# BLDC.net
KiCad netlist of a schematic drawn in Altium Designer
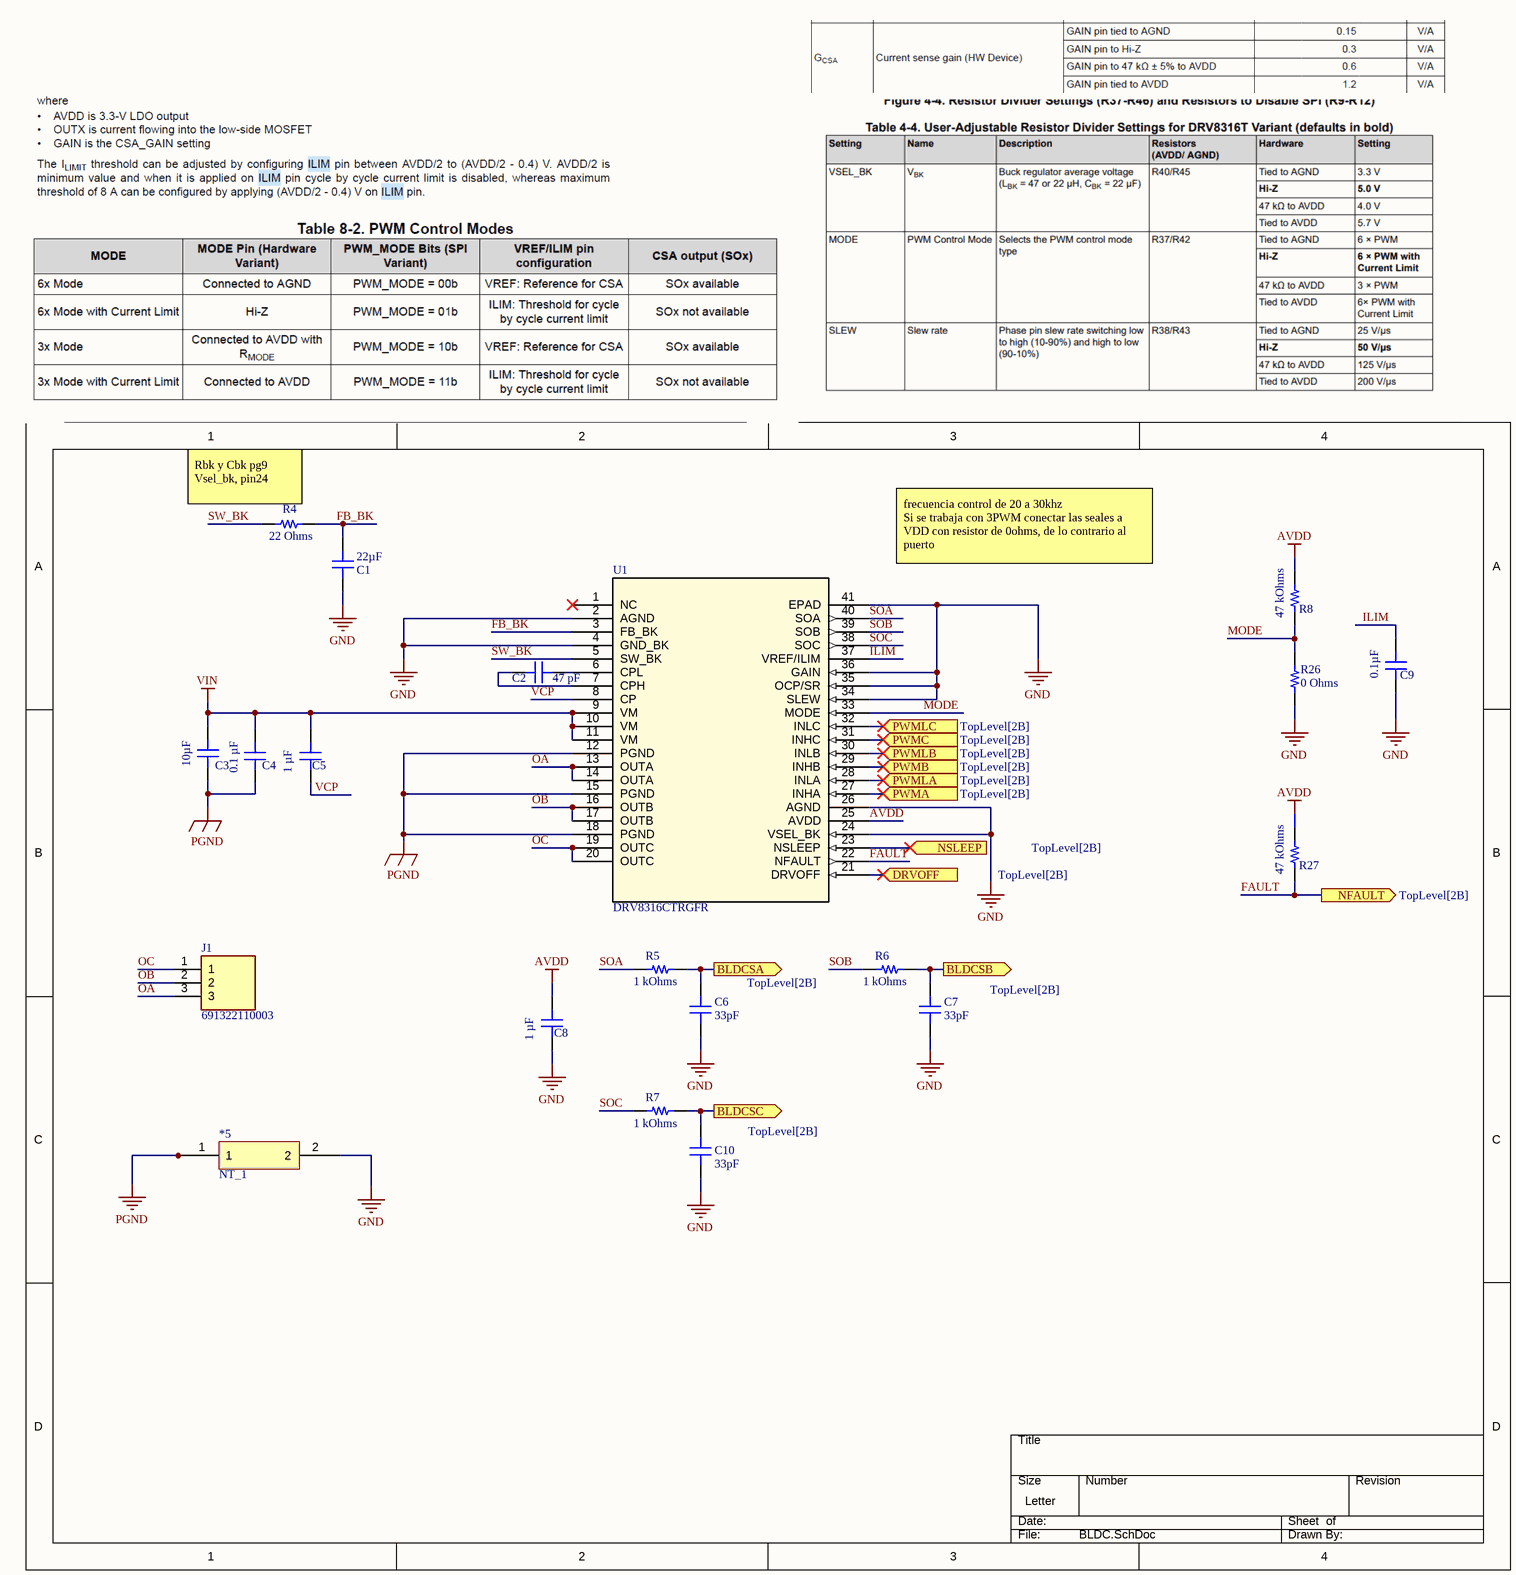
[diagram p0: BLDC.SchDoc]

(export (version "E")
  (design (tool "Eeschema 10.0.6"))
  (components
    (comp (ref "*5") (value "NT_1") (footprint "Net_Tie") (libsource (lib "net_tie") (part "NT_1")))
    (comp (ref "C1")
      (value "22µF")
      (footprint "CAP 0805_2012")
      (description "CAP CER 22UF 10V X5R 0805")
      (fields (field (name "TOLERANCE") "±20%") (field (name "PART NUMBER") "0805ZD226MAT2A"))
      (libsource (lib "Celestial Altium Library - altium_library") (part "Capacitor"))
    )
    (comp (ref "C2")
      (value "47 pF")
      (footprint "CAP 0805_2012")
      (description "CAP CER 47PF 50V C0G/NPO 0805")
      (fields (field (name "TOLERANCE") "±5%") (field (name "PART NUMBER") "AC0805JRNPO9BN470"))
      (libsource (lib "Celestial Altium Library - altium_library") (part "Capacitor"))
    )
    (comp (ref "C3")
      (value "10µF")
      (footprint "CAP 1210_3225 - 2.8MM")
      (description "CAP CER 10UF 35V X5R 1210")
      (fields (field (name "TOLERANCE") "±10%") (field (name "MANUFACTURER") "AVX Corporation"))
      (libsource (lib "Celestial Altium Library - altium_library") (part "Capacitor"))
    )
    (comp (ref "C4")
      (value "0.1 µF")
      (footprint "CAP 0603_1608")
      (description "CAP CER 0.1UF 35V X7R 0603")
      (fields (field (name "TOLERANCE") "±10%") (field (name "PART NUMBER") "GMJ107BB7104KAHT"))
      (libsource (lib "Celestial Altium Library - altium_library") (part "Capacitor"))
    )
    (comp (ref "C5")
      (value "~")
      (footprint "CAP 0805_2012")
      (description "CAP CER 1UF 50V Y5V 0805")
      (fields
        (field (name "TOLERANCE") "±20%")
        (field (name "PART NUMBER") "CC0805MKY5V9BB105")
        (field (name "CAPACITANCE") "1 µF")
      )
      (libsource (lib "Celestial Altium Library - altium_library") (part "Capacitor"))
    )
    (comp (ref "C6")
      (value "33pF")
      (footprint "CAP 0603_1608")
      (description "CAP CER 33PF 16V X7R 0603")
      (fields (field (name "TOLERANCE") "±5%") (field (name "PART NUMBER") "0603YC330JAT2A"))
      (libsource (lib "Celestial Altium Library - altium_library") (part "Capacitor"))
    )
    (comp (ref "C7")
      (value "33pF")
      (footprint "CAP 0603_1608")
      (description "CAP CER 33PF 16V X7R 0603")
      (fields (field (name "TOLERANCE") "±5%") (field (name "PART NUMBER") "0603YC330JAT2A"))
      (libsource (lib "Celestial Altium Library - altium_library") (part "Capacitor"))
    )
    (comp (ref "C8")
      (value "~")
      (footprint "CAP 0805_2012")
      (description "CAP CER 1UF 50V Y5V 0805")
      (fields
        (field (name "TOLERANCE") "±20%")
        (field (name "PART NUMBER") "CC0805MKY5V9BB105")
        (field (name "CAPACITANCE") "1 µF")
      )
      (libsource (lib "Celestial Altium Library - altium_library") (part "Capacitor"))
    )
    (comp (ref "C9")
      (value "~")
      (footprint "CAP 0805_2012")
      (description "CAP CER 0.1UF 25V Z5U 0805")
      (fields
        (field (name "TOLERANCE") "-20%, +80%")
        (field (name "PART NUMBER") "08053E104ZAT2A")
        (field (name "CAPACITANCE") "0.1µF")
      )
      (libsource (lib "Celestial Altium Library - altium_library") (part "Capacitor"))
    )
    (comp (ref "C10")
      (value "33pF")
      (footprint "CAP 0603_1608")
      (description "CAP CER 33PF 16V X7R 0603")
      (fields (field (name "TOLERANCE") "±5%") (field (name "PART NUMBER") "0603YC330JAT2A"))
      (libsource (lib "Celestial Altium Library - altium_library") (part "Capacitor"))
    )
    (comp (ref "J1")
      (value "691322110003")
      (footprint "SHDRRA3W80P0X350_1X3_1190X920X700P")
      (fields (field (name "MOUSER PART NUMBER") "710-691322110003"))
      (libsource (lib "691322110003") (part "691322110003"))
    )
    (comp (ref "R4")
      (value "22 Ohms")
      (footprint "YAGEO RES 0603_1608")
      (description "RES SMD 22 OHM 1% 1/10W 0603")
      (fields (field (name "TOLERANCE") "±1%") (field (name "PART NUMBER") "AC0603FR-0722RL"))
      (libsource (lib "Celestial Altium Library - altium_library") (part "Resistor"))
    )
    (comp (ref "R5")
      (value "1 kOhms")
      (footprint "YAGEO RES 0603_1608")
      (description "RES SMD 1K OHM 0.5% 1/10W 0603")
      (fields (field (name "PART NUMBER") "AT0603DRD071KL") (field (name "MANUFACTURER") "Yageo"))
      (libsource (lib "Celestial Altium Library - altium_library") (part "Resistor"))
    )
    (comp (ref "R6")
      (value "1 kOhms")
      (footprint "YAGEO RES 0603_1608")
      (description "RES SMD 1K OHM 0.5% 1/10W 0603")
      (fields (field (name "PART NUMBER") "AT0603DRD071KL") (field (name "MANUFACTURER") "Yageo"))
      (libsource (lib "Celestial Altium Library - altium_library") (part "Resistor"))
    )
    (comp (ref "R7")
      (value "1 kOhms")
      (footprint "YAGEO RES 0603_1608")
      (description "RES SMD 1K OHM 0.5% 1/10W 0603")
      (fields (field (name "PART NUMBER") "AT0603DRD071KL") (field (name "MANUFACTURER") "Yageo"))
      (libsource (lib "Celestial Altium Library - altium_library") (part "Resistor"))
    )
    (comp (ref "R8")
      (value "47 kOhms")
      (footprint "YAGEO RES 0603_1608")
      (description "RES SMD 47K OHM 1% 1/10W 0603")
      (fields (field (name "TOLERANCE") "±1%") (field (name "PART NUMBER") "RT0603FRE0747KL"))
      (libsource (lib "Celestial Altium Library - altium_library") (part "Resistor"))
    )
    (comp (ref "R26")
      (value "0 Ohms")
      (footprint "YAGEO RES 0603_1608")
      (description "RES 0 OHM JUMPER 1/10W 0603")
      (fields (field (name "PART NUMBER") "RC0603FR-100RL") (field (name "MANUFACTURER") "Yageo"))
      (libsource (lib "Celestial Altium Library - altium_library") (part "Resistor"))
    )
    (comp (ref "R27")
      (value "47 kOhms")
      (footprint "YAGEO RES 0603_1608")
      (description "RES SMD 47K OHM 1% 1/10W 0603")
      (fields (field (name "TOLERANCE") "±1%") (field (name "PART NUMBER") "RT0603FRE0747KL"))
      (libsource (lib "Celestial Altium Library - altium_library") (part "Resistor"))
    )
    (comp (ref "U1")
      (value "DRV8316CTRGFR")
      (footprint "VQFN40_RGF_TEX")
      (description "No Description Available")
      (fields (field (name "COPYRIGHT") "Copyright (C) 2024 Ultra Librarian. All rights reserved."))
      (libsource (lib "DRV8316CTRGFR") (part "DRV8316CTRGFR"))
    )
  )
  (nets
    (net (code "1") (name "/BLDCSA") (class "Default")
      (node (ref "C6") (pin "2") (pinfunction "2_2") (pintype "passive"))
      (node (ref "R5") (pin "2") (pinfunction "2_2") (pintype "passive"))
    )
    (net (code "2") (name "/BLDCSB") (class "Default")
      (node (ref "C7") (pin "2") (pinfunction "2_2") (pintype "passive"))
      (node (ref "R6") (pin "2") (pinfunction "2_2") (pintype "passive"))
    )
    (net (code "3") (name "/BLDCSC") (class "Default")
      (node (ref "C10") (pin "2") (pinfunction "2_2") (pintype "passive"))
      (node (ref "R7") (pin "2") (pinfunction "2_2") (pintype "passive"))
    )
    (net (code "4") (name "/DRVOFF") (class "Default")
      (node (ref "U1") (pin "21") (pinfunction "DRVOFF_21") (pintype "input+no_connect"))
    )
    (net (code "5") (name "/FAULT") (class "Default")
      (node (ref "R27") (pin "1") (pinfunction "1_1") (pintype "passive"))
      (node (ref "U1") (pin "22") (pinfunction "NFAULT_22") (pintype "output"))
    )
    (net (code "6") (name "/FB_BK") (class "Default")
      (node (ref "C1") (pin "1") (pinfunction "1_1") (pintype "passive"))
      (node (ref "R4") (pin "2") (pinfunction "2_2") (pintype "passive"))
      (node (ref "U1") (pin "3") (pinfunction "FB_BK_3") (pintype "power_in"))
    )
    (net (code "7") (name "/ILIM") (class "Default")
      (node (ref "C9") (pin "1") (pinfunction "1_1") (pintype "passive"))
      (node (ref "U1") (pin "37") (pinfunction "VREF/ILIM_37") (pintype "power_in"))
    )
    (net (code "8") (name "/MODE") (class "Default")
      (node (ref "R26") (pin "1") (pinfunction "1_1") (pintype "passive"))
      (node (ref "R8") (pin "1") (pinfunction "1_1") (pintype "passive"))
      (node (ref "U1") (pin "33") (pinfunction "MODE_33") (pintype "input"))
    )
    (net (code "9") (name "/NSLEEP") (class "Default")
      (node (ref "U1") (pin "23") (pinfunction "NSLEEP_23") (pintype "input+no_connect"))
    )
    (net (code "10") (name "/OA") (class "Default")
      (node (ref "J1") (pin "3") (pinfunction "3_3") (pintype "passive"))
      (node (ref "U1") (pin "13") (pinfunction "OUTA_13") (pintype "power_in"))
      (node (ref "U1") (pin "14") (pinfunction "OUTA_14") (pintype "power_in"))
    )
    (net (code "11") (name "/OB") (class "Default")
      (node (ref "J1") (pin "2") (pinfunction "2_2") (pintype "passive"))
      (node (ref "U1") (pin "16") (pinfunction "OUTB_16") (pintype "power_in"))
      (node (ref "U1") (pin "17") (pinfunction "OUTB_17") (pintype "power_in"))
    )
    (net (code "12") (name "/OC") (class "Default")
      (node (ref "J1") (pin "1") (pinfunction "1_1") (pintype "passive"))
      (node (ref "U1") (pin "19") (pinfunction "OUTC_19") (pintype "power_in"))
      (node (ref "U1") (pin "20") (pinfunction "OUTC_20") (pintype "power_in"))
    )
    (net (code "13") (name "/PWMA") (class "Default")
      (node (ref "U1") (pin "27") (pinfunction "INHA_27") (pintype "input+no_connect"))
    )
    (net (code "14") (name "/PWMB") (class "Default")
      (node (ref "U1") (pin "29") (pinfunction "INHB_29") (pintype "input+no_connect"))
    )
    (net (code "15") (name "/PWMC") (class "Default")
      (node (ref "U1") (pin "31") (pinfunction "INHC_31") (pintype "input+no_connect"))
    )
    (net (code "16") (name "/PWMLA") (class "Default")
      (node (ref "U1") (pin "28") (pinfunction "INLA_28") (pintype "input+no_connect"))
    )
    (net (code "17") (name "/PWMLB") (class "Default")
      (node (ref "U1") (pin "30") (pinfunction "INLB_30") (pintype "input+no_connect"))
    )
    (net (code "18") (name "/PWMLC") (class "Default")
      (node (ref "U1") (pin "32") (pinfunction "INLC_32") (pintype "input+no_connect"))
    )
    (net (code "19") (name "/SOA") (class "Default")
      (node (ref "R5") (pin "1") (pinfunction "1_1") (pintype "passive"))
      (node (ref "U1") (pin "40") (pinfunction "SOA_40") (pintype "output"))
    )
    (net (code "20") (name "/SOB") (class "Default")
      (node (ref "R6") (pin "1") (pinfunction "1_1") (pintype "passive"))
      (node (ref "U1") (pin "39") (pinfunction "SOB_39") (pintype "output"))
    )
    (net (code "21") (name "/SOC") (class "Default")
      (node (ref "R7") (pin "1") (pinfunction "1_1") (pintype "passive"))
      (node (ref "U1") (pin "38") (pinfunction "SOC_38") (pintype "output"))
    )
    (net (code "22") (name "/SW_BK") (class "Default")
      (node (ref "R4") (pin "1") (pinfunction "1_1") (pintype "passive"))
      (node (ref "U1") (pin "5") (pinfunction "SW_BK_5") (pintype "power_in"))
    )
    (net (code "23") (name "/VCP") (class "Default")
      (node (ref "C5") (pin "2") (pinfunction "2_2") (pintype "passive"))
      (node (ref "U1") (pin "8") (pinfunction "CP_8") (pintype "power_in"))
    )
    (net (code "24") (name "AVDD") (class "Default")
      (node (ref "C8") (pin "1") (pinfunction "1_1") (pintype "passive"))
      (node (ref "R27") (pin "2") (pinfunction "2_2") (pintype "passive"))
      (node (ref "R8") (pin "2") (pinfunction "2_2") (pintype "passive"))
      (node (ref "U1") (pin "25") (pinfunction "AVDD_25") (pintype "power_in"))
    )
    (net (code "25") (name "GND") (class "Default")
      (node (ref "*5") (pin "2") (pinfunction "2_2") (pintype "passive"))
      (node (ref "C1") (pin "2") (pinfunction "2_2") (pintype "passive"))
      (node (ref "C10") (pin "1") (pinfunction "1_1") (pintype "passive"))
      (node (ref "C6") (pin "1") (pinfunction "1_1") (pintype "passive"))
      (node (ref "C7") (pin "1") (pinfunction "1_1") (pintype "passive"))
      (node (ref "C8") (pin "2") (pinfunction "2_2") (pintype "passive"))
      (node (ref "C9") (pin "2") (pinfunction "2_2") (pintype "passive"))
      (node (ref "R26") (pin "2") (pinfunction "2_2") (pintype "passive"))
      (node (ref "U1") (pin "2") (pinfunction "AGND_2") (pintype "power_in"))
      (node (ref "U1") (pin "24") (pinfunction "VSEL_BK_24") (pintype "input"))
      (node (ref "U1") (pin "26") (pinfunction "AGND_26") (pintype "power_in"))
      (node (ref "U1") (pin "34") (pinfunction "SLEW_34") (pintype "input"))
      (node (ref "U1") (pin "35") (pinfunction "OCP/SR_35") (pintype "input"))
      (node (ref "U1") (pin "36") (pinfunction "GAIN_36") (pintype "input"))
      (node (ref "U1") (pin "4") (pinfunction "GND_BK_4") (pintype "power_in"))
      (node (ref "U1") (pin "41") (pinfunction "EPAD_41") (pintype "power_in"))
    )
    (net (code "26") (name "Net-(U1-CPH)") (class "Default")
      (node (ref "C2") (pin "1") (pinfunction "1_1") (pintype "passive"))
      (node (ref "U1") (pin "7") (pinfunction "CPH_7") (pintype "power_in"))
    )
    (net (code "27") (name "Net-(U1-CPL)") (class "Default")
      (node (ref "C2") (pin "2") (pinfunction "2_2") (pintype "passive"))
      (node (ref "U1") (pin "6") (pinfunction "CPL_6") (pintype "power_in"))
    )
    (net (code "28") (name "PGND") (class "Default")
      (node (ref "*5") (pin "1") (pinfunction "1_1") (pintype "passive"))
      (node (ref "C3") (pin "1") (pinfunction "1_1") (pintype "passive"))
      (node (ref "C4") (pin "2") (pinfunction "2_2") (pintype "passive"))
      (node (ref "U1") (pin "12") (pinfunction "PGND_12") (pintype "power_in"))
      (node (ref "U1") (pin "15") (pinfunction "PGND_15") (pintype "power_in"))
      (node (ref "U1") (pin "18") (pinfunction "PGND_18") (pintype "power_in"))
    )
    (net (code "29") (name "VIN") (class "Default")
      (node (ref "C3") (pin "2") (pinfunction "2_2") (pintype "passive"))
      (node (ref "C4") (pin "1") (pinfunction "1_1") (pintype "passive"))
      (node (ref "C5") (pin "1") (pinfunction "1_1") (pintype "passive"))
      (node (ref "U1") (pin "10") (pinfunction "VM_10") (pintype "power_in"))
      (node (ref "U1") (pin "11") (pinfunction "VM_11") (pintype "power_in"))
      (node (ref "U1") (pin "9") (pinfunction "VM_9") (pintype "power_in"))
    )
    (net (code "30") (name "unconnected-(U1-NC-Pad1)") (class "Default")
      (node (ref "U1") (pin "1") (pinfunction "NC_1") (pintype "passive+no_connect"))
    )
  )
)
